# MPU9250.net
KiCad netlist of a schematic drawn in Altium Designer
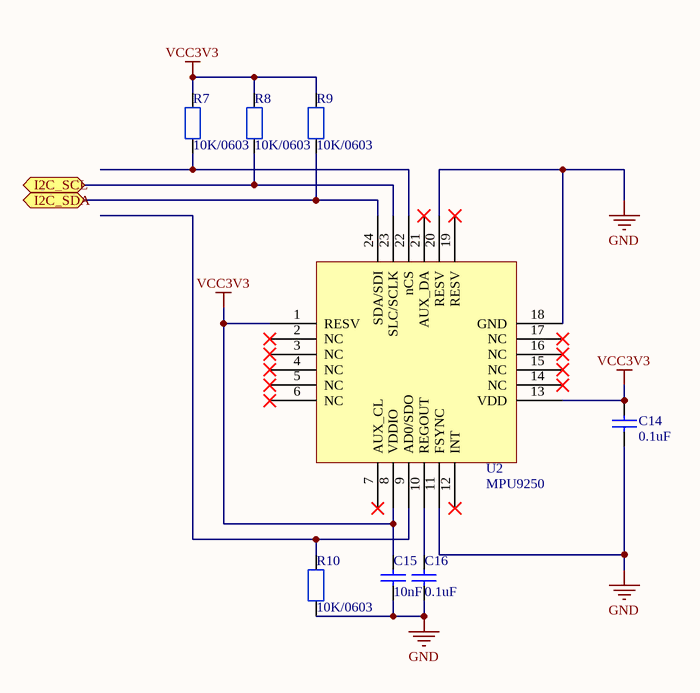
[diagram p0: MPU9250.SchDoc]

(export (version "E")
  (design (tool "Eeschema 10.0.6"))
  (components
    (comp (ref "C14")
      (value "0.1uF")
      (footprint "C0603")
      (description "无极性贴片电容")
      (libsource (lib "常用原件") (part "CAP"))
    )
    (comp (ref "C15")
      (value "10nF")
      (footprint "C0603")
      (description "无极性贴片电容")
      (libsource (lib "常用原件") (part "CAP"))
    )
    (comp (ref "C16")
      (value "0.1uF")
      (footprint "C0603")
      (description "无极性贴片电容")
      (libsource (lib "常用原件") (part "CAP"))
    )
    (comp (ref "R7") (value "10K/0603") (footprint "R0603") (libsource (lib "常用原件") (part "RES")))
    (comp (ref "R8") (value "10K/0603") (footprint "R0603") (libsource (lib "常用原件") (part "RES")))
    (comp (ref "R9") (value "10K/0603") (footprint "R0603") (libsource (lib "常用原件") (part "RES")))
    (comp (ref "R10") (value "10K/0603") (footprint "R0603") (libsource (lib "常用原件") (part "RES")))
    (comp (ref "U2") (value "MPU9250") (footprint "QFN24") (libsource (lib "Schlib1") (part "MPU9250")))
  )
  (nets
    (net (code "1") (name "/I2C_SCL") (class "Default")
      (node (ref "R8") (pin "1") (pinfunction "1_1") (pintype "passive"))
      (node (ref "U2") (pin "23") (pinfunction "SLC/SCLK_23") (pintype "passive"))
    )
    (net (code "2") (name "/I2C_SDA") (class "Default")
      (node (ref "R9") (pin "1") (pinfunction "1_1") (pintype "passive"))
      (node (ref "U2") (pin "24") (pinfunction "SDA/SDI_24") (pintype "passive"))
    )
    (net (code "3") (name "GND") (class "Default")
      (node (ref "C14") (pin "1") (pinfunction "1_1") (pintype "passive"))
      (node (ref "C15") (pin "1") (pinfunction "1_1") (pintype "passive"))
      (node (ref "C16") (pin "1") (pinfunction "1_1") (pintype "passive"))
      (node (ref "R10") (pin "1") (pinfunction "1_1") (pintype "passive"))
      (node (ref "U2") (pin "11") (pinfunction "FSYNC_11") (pintype "passive"))
      (node (ref "U2") (pin "18") (pinfunction "GND_18") (pintype "passive"))
      (node (ref "U2") (pin "20") (pinfunction "RESV_20") (pintype "passive"))
    )
    (net (code "4") (name "Net-(U2-AD0{slash}SDO)") (class "Default")
      (node (ref "R10") (pin "2") (pinfunction "2_2") (pintype "passive"))
      (node (ref "U2") (pin "9") (pinfunction "AD0/SDO_9") (pintype "passive"))
    )
    (net (code "5") (name "Net-(U2-REGOUT)") (class "Default")
      (node (ref "C16") (pin "2") (pinfunction "2_2") (pintype "passive"))
      (node (ref "U2") (pin "10") (pinfunction "REGOUT_10") (pintype "passive"))
    )
    (net (code "6") (name "Net-(U2-nCS)") (class "Default")
      (node (ref "R7") (pin "1") (pinfunction "1_1") (pintype "passive"))
      (node (ref "U2") (pin "22") (pinfunction "nCS_22") (pintype "passive"))
    )
    (net (code "7") (name "VCC3V3") (class "Default")
      (node (ref "C14") (pin "2") (pinfunction "2_2") (pintype "passive"))
      (node (ref "C15") (pin "2") (pinfunction "2_2") (pintype "passive"))
      (node (ref "R7") (pin "2") (pinfunction "2_2") (pintype "passive"))
      (node (ref "R8") (pin "2") (pinfunction "2_2") (pintype "passive"))
      (node (ref "R9") (pin "2") (pinfunction "2_2") (pintype "passive"))
      (node (ref "U2") (pin "1") (pinfunction "RESV_1") (pintype "passive"))
      (node (ref "U2") (pin "13") (pinfunction "VDD_13") (pintype "passive"))
      (node (ref "U2") (pin "8") (pinfunction "VDDIO_8") (pintype "passive"))
    )
    (net (code "8") (name "unconnected-(U2-AUX_CL-Pad7)") (class "Default")
      (node (ref "U2") (pin "7") (pinfunction "AUX_CL_7") (pintype "passive+no_connect"))
    )
    (net (code "9") (name "unconnected-(U2-AUX_DA-Pad21)") (class "Default")
      (node (ref "U2") (pin "21") (pinfunction "AUX_DA_21") (pintype "passive+no_connect"))
    )
    (net (code "10") (name "unconnected-(U2-INT-Pad12)") (class "Default")
      (node (ref "U2") (pin "12") (pinfunction "INT_12") (pintype "passive+no_connect"))
    )
    (net (code "11") (name "unconnected-(U2-NC-Pad2)") (class "Default")
      (node (ref "U2") (pin "2") (pinfunction "NC_2") (pintype "passive+no_connect"))
    )
    (net (code "12") (name "unconnected-(U2-NC-Pad3)") (class "Default")
      (node (ref "U2") (pin "3") (pinfunction "NC_3") (pintype "passive+no_connect"))
    )
    (net (code "13") (name "unconnected-(U2-NC-Pad4)") (class "Default")
      (node (ref "U2") (pin "4") (pinfunction "NC_4") (pintype "passive+no_connect"))
    )
    (net (code "14") (name "unconnected-(U2-NC-Pad5)") (class "Default")
      (node (ref "U2") (pin "5") (pinfunction "NC_5") (pintype "passive+no_connect"))
    )
    (net (code "15") (name "unconnected-(U2-NC-Pad6)") (class "Default")
      (node (ref "U2") (pin "6") (pinfunction "NC_6") (pintype "passive+no_connect"))
    )
    (net (code "16") (name "unconnected-(U2-NC-Pad14)") (class "Default")
      (node (ref "U2") (pin "14") (pinfunction "NC_14") (pintype "passive+no_connect"))
    )
    (net (code "17") (name "unconnected-(U2-NC-Pad15)") (class "Default")
      (node (ref "U2") (pin "15") (pinfunction "NC_15") (pintype "passive+no_connect"))
    )
    (net (code "18") (name "unconnected-(U2-NC-Pad16)") (class "Default")
      (node (ref "U2") (pin "16") (pinfunction "NC_16") (pintype "passive+no_connect"))
    )
    (net (code "19") (name "unconnected-(U2-NC-Pad17)") (class "Default")
      (node (ref "U2") (pin "17") (pinfunction "NC_17") (pintype "passive+no_connect"))
    )
    (net (code "20") (name "unconnected-(U2-RESV-Pad19)") (class "Default")
      (node (ref "U2") (pin "19") (pinfunction "RESV_19") (pintype "passive+no_connect"))
    )
  )
)
